# Motor_Controller.net
KiCad netlist of a schematic drawn in Altium Designer
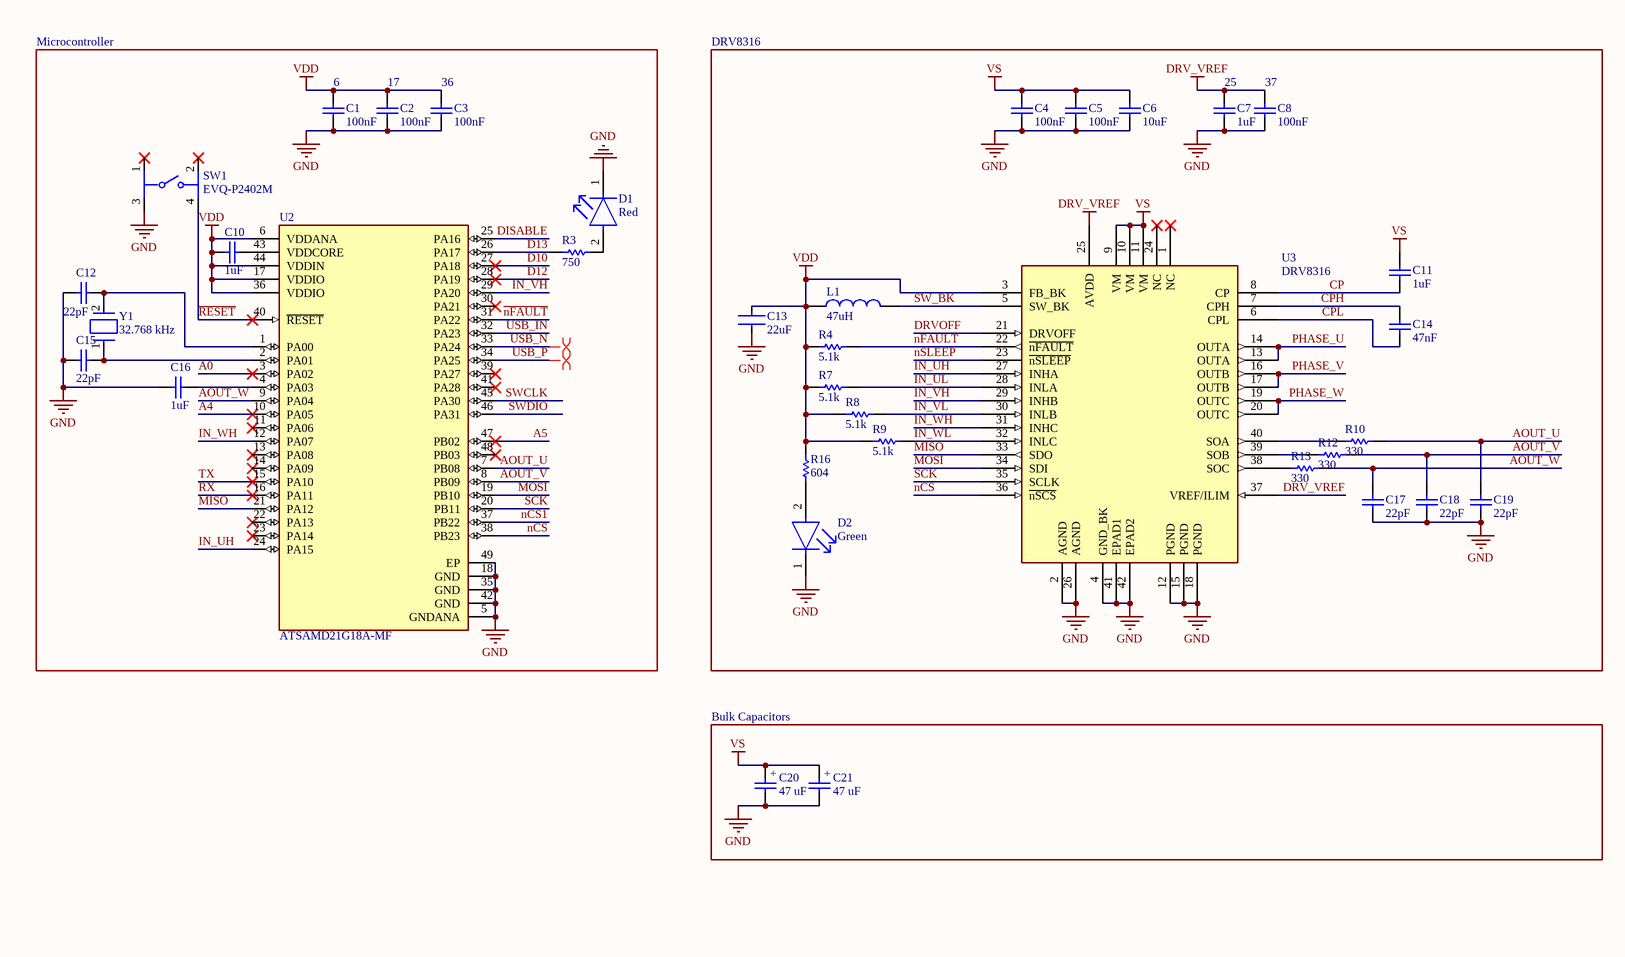
[diagram p0: Motor Controller.SchDoc, left]
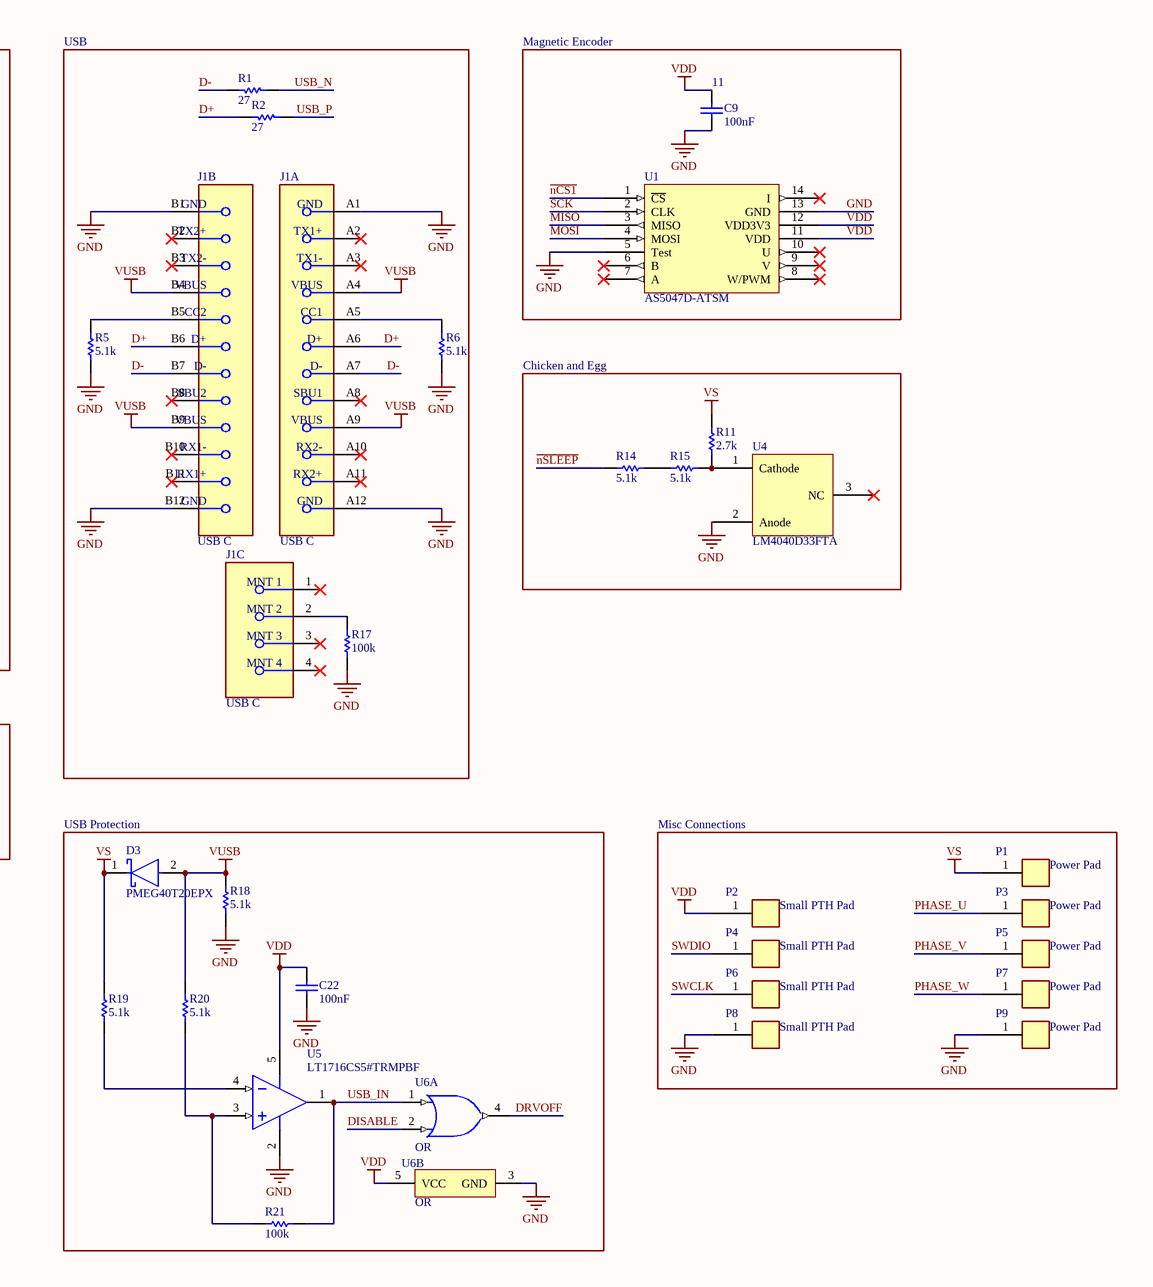
[diagram p1: Motor Controller.SchDoc, right]

(export (version "E")
  (design (tool "Eeschema 10.0.6"))
  (components
    (comp (ref "C1")
      (value "100nF")
      (footprint "0402CAP")
      (libsource (lib "Main") (part "GCM155R71H104KE02D"))
    )
    (comp (ref "C2")
      (value "100nF")
      (footprint "0402CAP")
      (libsource (lib "Main") (part "GCM155R71H104KE02D"))
    )
    (comp (ref "C3")
      (value "100nF")
      (footprint "0402CAP")
      (libsource (lib "Main") (part "GCM155R71H104KE02D"))
    )
    (comp (ref "C4")
      (value "100nF")
      (footprint "0402CAP")
      (libsource (lib "Main") (part "GCM155R71H104KE02D"))
    )
    (comp (ref "C5")
      (value "100nF")
      (footprint "0402CAP")
      (libsource (lib "Main") (part "GCM155R71H104KE02D"))
    )
    (comp (ref "C6")
      (value "10uF")
      (footprint "FP-GRT31C-0_2-IPC_B")
      (libsource (lib "Main") (part "GRT31CR61H106ME01L"))
    )
    (comp (ref "C7") (value "1uF") (footprint "0603CAP") (libsource (lib "Main") (part "GRT188R61H105ME13D")))
    (comp (ref "C8")
      (value "100nF")
      (footprint "0402CAP")
      (libsource (lib "Main") (part "GCM155R71H104KE02D"))
    )
    (comp (ref "C9")
      (value "100nF")
      (footprint "0402CAP")
      (libsource (lib "Main") (part "GCM155R71H104KE02D"))
    )
    (comp (ref "C10")
      (value "1uF")
      (footprint "0603CAP")
      (libsource (lib "Main") (part "GRT188R61H105ME13D"))
    )
    (comp (ref "C11")
      (value "1uF")
      (footprint "0603CAP")
      (libsource (lib "Main") (part "GRT188R61H105ME13D"))
    )
    (comp (ref "C12")
      (value "22pF")
      (footprint "0402CAP")
      (libsource (lib "Main") (part "C0402C220J5GAC7411"))
    )
    (comp (ref "C13")
      (value "22uF")
      (footprint "FP-GRM319-0_15-MFG")
      (description "Multilayer Ceramic Capacitors 22uF ±10% 16V X7R SMD 1210")
      (fields (field (name "VOLTAGE") "16V") (field (name "TOLERANCE") "10%"))
      (libsource (lib "Main") (part "GRM319R61C226ME15D"))
    )
    (comp (ref "C14")
      (value "47nF")
      (footprint "FP-GRM155-0_05-MFG")
      (description "Chip Capacitor, 47 nF, +/- 10%, 50 V, -55 to 125 degC, 0402 (1005 Metric), RoHS, Tape and Reel")
      (fields (field (name "TOLERANCE") "±10%") (field (name "MANUFACTURER") "TDK"))
      (libsource (lib "Main") (part "GRM155R71H473KE14D"))
    )
    (comp (ref "C15")
      (value "22pF")
      (footprint "0402CAP")
      (libsource (lib "Main") (part "C0402C220J5GAC7411"))
    )
    (comp (ref "C16")
      (value "1uF")
      (footprint "0603CAP")
      (libsource (lib "Main") (part "GRT188R61H105ME13D"))
    )
    (comp (ref "C17")
      (value "22pF")
      (footprint "0402CAP")
      (libsource (lib "Main") (part "C0402C220J5GAC7411"))
    )
    (comp (ref "C18")
      (value "22pF")
      (footprint "0402CAP")
      (libsource (lib "Main") (part "C0402C220J5GAC7411"))
    )
    (comp (ref "C19")
      (value "22pF")
      (footprint "0402CAP")
      (libsource (lib "Main") (part "C0402C220J5GAC7411"))
    )
    (comp (ref "C20")
      (value "47 uF")
      (footprint "CAPAE7866X61N")
      (libsource (lib "Main") (part "EEE-FT1H470AL"))
    )
    (comp (ref "C21")
      (value "47 uF")
      (footprint "CAPAE7866X61N")
      (libsource (lib "Main") (part "EEE-FT1H470AL"))
    )
    (comp (ref "C22")
      (value "100nF")
      (footprint "0402CAP")
      (libsource (lib "Main") (part "GCM155R71H104KE02D"))
    )
    (comp (ref "D1")
      (value "Red")
      (footprint "FP-APT1608LSECK-J3-PRV-MFG")
      (description "LED RED CLEAR 2SMD")
      (libsource (lib "Main") (part "APT1608LSECK/J3-PRV"))
    )
    (comp (ref "D2")
      (value "Green")
      (footprint "FP-APT1608MGC-MFG")
      (description "LED GREEN CLEAR CHIP SMD")
      (libsource (lib "Main") (part "APT1608MGC"))
    )
    (comp (ref "D3")
      (value "PMEG40T20EPX")
      (footprint "SODFL470X110-2N")
      (libsource (lib "Main") (part "PMEG40T20EPX"))
    )
    (comp (ref "J1")
      (value "USB C")
      (footprint "FP-1054500101-MFG")
      (description "CONN RCP USB3.1 TYPEC 24P SMD RA")
      (fields
        (field (name "MANUFACTURER") "Molex")
        (field (name "OCTOPART") "https://octopart.com/105450-0101-molex-68082325")
      )
      (libsource (lib "Main") (part "1054500101"))
    )
    (comp (ref "L1")
      (value "47uH")
      (footprint "INDC3225X25N")
      (libsource (lib "Main") (part "L1210R470KDWIT"))
    )
    (comp (ref "P1") (value "Power Pad") (footprint "Power Pad") (libsource (lib "Main") (part "Power Pad")))
    (comp (ref "P2")
      (value "Small PTH Pad")
      (footprint "Small PTH Pad")
      (libsource (lib "Main") (part "Small PTH Pad"))
    )
    (comp (ref "P3") (value "Power Pad") (footprint "Power Pad") (libsource (lib "Main") (part "Power Pad")))
    (comp (ref "P4")
      (value "Small PTH Pad")
      (footprint "Small PTH Pad")
      (libsource (lib "Main") (part "Small PTH Pad"))
    )
    (comp (ref "P5") (value "Power Pad") (footprint "Power Pad") (libsource (lib "Main") (part "Power Pad")))
    (comp (ref "P6")
      (value "Small PTH Pad")
      (footprint "Small PTH Pad")
      (libsource (lib "Main") (part "Small PTH Pad"))
    )
    (comp (ref "P7") (value "Power Pad") (footprint "Power Pad") (libsource (lib "Main") (part "Power Pad")))
    (comp (ref "P8")
      (value "Small PTH Pad")
      (footprint "Small PTH Pad")
      (libsource (lib "Main") (part "Small PTH Pad"))
    )
    (comp (ref "P9") (value "Power Pad") (footprint "Power Pad") (libsource (lib "Main") (part "Power Pad")))
    (comp (ref "R1")
      (value "27")
      (footprint "RESC1005X40X25LL05T05")
      (libsource (lib "Main") (part "ERJ2RKD27R0X"))
    )
    (comp (ref "R2")
      (value "27")
      (footprint "RESC1005X40X25LL05T05")
      (libsource (lib "Main") (part "ERJ2RKD27R0X"))
    )
    (comp (ref "R3")
      (value "750")
      (footprint "RESC1005X40X25LL05T05")
      (libsource (lib "Main") (part "ERJ-2RKF7500X"))
    )
    (comp (ref "R4")
      (value "5.1k")
      (footprint "RESC1005X40X25LL05T05")
      (fields (field (name "TOLERANCE") "1%") (field (name "PARTNUMBER") "ERJ-2RKF4701X"))
      (libsource (lib "Main") (part "ERJ-2RKF5101X"))
    )
    (comp (ref "R5")
      (value "5.1k")
      (footprint "RESC1005X40X25LL05T05")
      (fields (field (name "TOLERANCE") "1%") (field (name "PARTNUMBER") "ERJ-2RKF4701X"))
      (libsource (lib "Main") (part "ERJ-2RKF5101X"))
    )
    (comp (ref "R6")
      (value "5.1k")
      (footprint "RESC1005X40X25LL05T05")
      (fields (field (name "TOLERANCE") "1%") (field (name "PARTNUMBER") "ERJ-2RKF4701X"))
      (libsource (lib "Main") (part "ERJ-2RKF5101X"))
    )
    (comp (ref "R7")
      (value "5.1k")
      (footprint "RESC1005X40X25LL05T05")
      (fields (field (name "TOLERANCE") "1%") (field (name "PARTNUMBER") "ERJ-2RKF4701X"))
      (libsource (lib "Main") (part "ERJ-2RKF5101X"))
    )
    (comp (ref "R8")
      (value "5.1k")
      (footprint "RESC1005X40X25LL05T05")
      (fields (field (name "TOLERANCE") "1%") (field (name "PARTNUMBER") "ERJ-2RKF4701X"))
      (libsource (lib "Main") (part "ERJ-2RKF5101X"))
    )
    (comp (ref "R9")
      (value "5.1k")
      (footprint "RESC1005X40X25LL05T05")
      (fields (field (name "TOLERANCE") "1%") (field (name "PARTNUMBER") "ERJ-2RKF4701X"))
      (libsource (lib "Main") (part "ERJ-2RKF5101X"))
    )
    (comp (ref "R10")
      (value "330")
      (footprint "RESC1005X40X25LL05T05")
      (fields (field (name "MANUFACTURER") "Panasonic") (field (name "PART NUMBER") "ERJ2RKF3300X"))
      (libsource (lib "Main") (part "ERJ2RKF3300X"))
    )
    (comp (ref "R11")
      (value "2.7k")
      (footprint "RESC1005X40X25LL05T05")
      (fields (field (name "PART NUMBER") "ERJ2RKF2701X") (field (name "MANUFACTURER") "Panasonic"))
      (libsource (lib "Main") (part "ERJ2RKF2701X"))
    )
    (comp (ref "R12")
      (value "330")
      (footprint "RESC1005X40X25LL05T05")
      (fields (field (name "MANUFACTURER") "Panasonic") (field (name "PART NUMBER") "ERJ2RKF3300X"))
      (libsource (lib "Main") (part "ERJ2RKF3300X"))
    )
    (comp (ref "R13")
      (value "330")
      (footprint "RESC1005X40X25LL05T05")
      (fields (field (name "MANUFACTURER") "Panasonic") (field (name "PART NUMBER") "ERJ2RKF3300X"))
      (libsource (lib "Main") (part "ERJ2RKF3300X"))
    )
    (comp (ref "R14")
      (value "5.1k")
      (footprint "RESC1005X40X25LL05T05")
      (fields (field (name "TOLERANCE") "1%") (field (name "PARTNUMBER") "ERJ-2RKF4701X"))
      (libsource (lib "Main") (part "ERJ-2RKF5101X"))
    )
    (comp (ref "R15")
      (value "5.1k")
      (footprint "RESC1005X40X25LL05T05")
      (fields (field (name "TOLERANCE") "1%") (field (name "PARTNUMBER") "ERJ-2RKF4701X"))
      (libsource (lib "Main") (part "ERJ-2RKF5101X"))
    )
    (comp (ref "R16")
      (value "604")
      (footprint "RESC1005X40X25LL05T05")
      (fields (field (name "PART NUMBER") "ERJ-2RKF6040X") (field (name "MANUFACTURER") "Panasonic"))
      (libsource (lib "Main") (part "ERJ-2RKF6040X"))
    )
    (comp (ref "R17")
      (value "100k")
      (footprint "RESC1005X40X25LL05T05")
      (libsource (lib "Main") (part "ERJ2RHD1003X"))
    )
    (comp (ref "R18")
      (value "5.1k")
      (footprint "RESC1005X40X25LL05T05")
      (fields (field (name "TOLERANCE") "1%") (field (name "PARTNUMBER") "ERJ-2RKF4701X"))
      (libsource (lib "Main") (part "ERJ-2RKF5101X"))
    )
    (comp (ref "R19")
      (value "5.1k")
      (footprint "RESC1005X40X25LL05T05")
      (fields (field (name "TOLERANCE") "1%") (field (name "PARTNUMBER") "ERJ-2RKF4701X"))
      (libsource (lib "Main") (part "ERJ-2RKF5101X"))
    )
    (comp (ref "R20")
      (value "5.1k")
      (footprint "RESC1005X40X25LL05T05")
      (fields (field (name "TOLERANCE") "1%") (field (name "PARTNUMBER") "ERJ-2RKF4701X"))
      (libsource (lib "Main") (part "ERJ-2RKF5101X"))
    )
    (comp (ref "R21")
      (value "100k")
      (footprint "RESC1005X40X25LL05T05")
      (libsource (lib "Main") (part "ERJ2RHD1003X"))
    )
    (comp (ref "SW1")
      (value "EVQ-P2402M")
      (footprint "EVQ-P2402M")
      (libsource (lib "Main") (part "EVQ-P2402M"))
    )
    (comp (ref "U1")
      (value "AS5047D-ATSM")
      (footprint "TSOP65P640X120-14N")
      (libsource (lib "Main") (part "AS5047D-ATSM"))
    )
    (comp (ref "U2")
      (value "ATSAMD21G18A-MF")
      (footprint "QFN-48")
      (libsource (lib "Main") (part "ATSAMD21G18A-MF"))
    )
    (comp (ref "U3")
      (value "DRV8316")
      (footprint "QFN50P500X700X100_HS-41L")
      (libsource (lib "Main") (part "DRV8316"))
    )
    (comp (ref "U4")
      (value "LM4040D33FTA")
      (footprint "SOT65P210X100-3N")
      (libsource (lib "Main") (part "LM4040D33FTA"))
    )
    (comp (ref "U5")
      (value "LT1716CS5#TRMPBF")
      (footprint "SOT95P280X100-5N")
      (fields (field (name "GENERIC PART NUMBER") "LT1716") (field (name "MANUFACTURER") "Linear Technology"))
      (libsource (lib "Main") (part "LT1716CS5#TRMPBF"))
    )
    (comp (ref "U6")
      (value "OR")
      (footprint "DBV0005A_M")
      (description "Single Power Supply 2-INPUT POSITIVE OR GATE with Logic Level Shifter, DBV0005A, LARGE T&R")
      (fields
        (field (name "GENERIC PART NUMBER") "SN74LV1T32")
        (field (name "MANUFACTURER") "Texas Instruments")
      )
      (libsource (lib "Main") (part "SN74LV1T32DBVR"))
    )
    (comp (ref "Y1")
      (value "32.768 kHz")
      (footprint "ABS05W-32.768KHZ-D-2-T")
      (description "Crystal Oscillator")
      (libsource (lib "Main") (part "ABS05W-32.768KHZ-D-2-T"))
    )
  )
  (nets
    (net (code "1") (name "/A0") (class "Default")
      (node (ref "U2") (pin "3") (pinfunction "PA02_3") (pintype "bidirectional+no_connect"))
    )
    (net (code "2") (name "/A4") (class "Default")
      (node (ref "U2") (pin "10") (pinfunction "PA05_10") (pintype "bidirectional+no_connect"))
    )
    (net (code "3") (name "/A5") (class "Default")
      (node (ref "U2") (pin "47") (pinfunction "PB02_47") (pintype "bidirectional+no_connect"))
    )
    (net (code "4") (name "/AOUT_U") (class "Default")
      (node (ref "C19") (pin "2") (pinfunction "2_2") (pintype "passive"))
      (node (ref "R10") (pin "2") (pinfunction "2_2") (pintype "passive"))
      (node (ref "U2") (pin "7") (pinfunction "PB08_7") (pintype "bidirectional"))
    )
    (net (code "5") (name "/AOUT_V") (class "Default")
      (node (ref "C18") (pin "2") (pinfunction "2_2") (pintype "passive"))
      (node (ref "R12") (pin "2") (pinfunction "2_2") (pintype "passive"))
      (node (ref "U2") (pin "8") (pinfunction "PB09_8") (pintype "bidirectional"))
    )
    (net (code "6") (name "/AOUT_W") (class "Default")
      (node (ref "C17") (pin "2") (pinfunction "2_2") (pintype "passive"))
      (node (ref "R13") (pin "2") (pinfunction "2_2") (pintype "passive"))
      (node (ref "U2") (pin "9") (pinfunction "PA04_9") (pintype "bidirectional"))
    )
    (net (code "7") (name "/CP") (class "Default")
      (node (ref "C11") (pin "1") (pinfunction "1_1") (pintype "passive"))
      (node (ref "U3") (pin "8") (pinfunction "CP_8") (pintype "power_in"))
    )
    (net (code "8") (name "/CPH") (class "Default")
      (node (ref "C14") (pin "2") (pinfunction "2_2") (pintype "passive"))
      (node (ref "U3") (pin "7") (pinfunction "CPH_7") (pintype "power_in"))
    )
    (net (code "9") (name "/CPL") (class "Default")
      (node (ref "C14") (pin "1") (pinfunction "1_1") (pintype "passive"))
      (node (ref "U3") (pin "6") (pinfunction "CPL_6") (pintype "power_in"))
    )
    (net (code "10") (name "/D+") (class "Default")
      (node (ref "J1") (pin "A6") (pinfunction "D+_A6") (pintype "passive"))
      (node (ref "J1") (pin "B6") (pinfunction "D+_B6") (pintype "passive"))
      (node (ref "R2") (pin "2") (pinfunction "2_2") (pintype "passive"))
    )
    (net (code "11") (name "/D-") (class "Default")
      (node (ref "J1") (pin "A7") (pinfunction "D-_A7") (pintype "passive"))
      (node (ref "J1") (pin "B7") (pinfunction "D-_B7") (pintype "passive"))
      (node (ref "R1") (pin "2") (pinfunction "2_2") (pintype "passive"))
    )
    (net (code "12") (name "/D10") (class "Default")
      (node (ref "U2") (pin "27") (pinfunction "PA18_27") (pintype "bidirectional+no_connect"))
    )
    (net (code "13") (name "/D12") (class "Default")
      (node (ref "U2") (pin "28") (pinfunction "PA19_28") (pintype "bidirectional+no_connect"))
    )
    (net (code "14") (name "/D13") (class "Default")
      (node (ref "R3") (pin "1") (pinfunction "1_1") (pintype "passive"))
      (node (ref "U2") (pin "26") (pinfunction "PA17_26") (pintype "bidirectional"))
    )
    (net (code "15") (name "/DISABLE") (class "Default")
      (node (ref "U2") (pin "25") (pinfunction "PA16_25") (pintype "bidirectional"))
      (node (ref "U6") (pin "2") (pinfunction "B_2") (pintype "input"))
    )
    (net (code "16") (name "/DRVOFF") (class "Default")
      (node (ref "U3") (pin "21") (pinfunction "DRVOFF_21") (pintype "input"))
      (node (ref "U6") (pin "4") (pinfunction "Y_4") (pintype "output"))
    )
    (net (code "17") (name "/IN_UH") (class "Default")
      (node (ref "U2") (pin "24") (pinfunction "PA15_24") (pintype "bidirectional"))
      (node (ref "U3") (pin "27") (pinfunction "INHA_27") (pintype "input"))
    )
    (net (code "18") (name "/IN_UL") (class "Default")
      (node (ref "R7") (pin "2") (pinfunction "2_2") (pintype "passive"))
      (node (ref "U3") (pin "28") (pinfunction "INLA_28") (pintype "input"))
    )
    (net (code "19") (name "/IN_VH") (class "Default")
      (node (ref "U2") (pin "29") (pinfunction "PA20_29") (pintype "bidirectional"))
      (node (ref "U3") (pin "29") (pinfunction "INHB_29") (pintype "input"))
    )
    (net (code "20") (name "/IN_VL") (class "Default")
      (node (ref "R8") (pin "2") (pinfunction "2_2") (pintype "passive"))
      (node (ref "U3") (pin "30") (pinfunction "INLB_30") (pintype "input"))
    )
    (net (code "21") (name "/IN_WH") (class "Default")
      (node (ref "U2") (pin "12") (pinfunction "PA07_12") (pintype "bidirectional"))
      (node (ref "U3") (pin "31") (pinfunction "INHC_31") (pintype "input"))
    )
    (net (code "22") (name "/IN_WL") (class "Default")
      (node (ref "R9") (pin "2") (pinfunction "2_2") (pintype "passive"))
      (node (ref "U3") (pin "32") (pinfunction "INLC_32") (pintype "input"))
    )
    (net (code "23") (name "/MISO") (class "Default")
      (node (ref "U1") (pin "3") (pinfunction "MISO_3") (pintype "output"))
      (node (ref "U2") (pin "21") (pinfunction "PA12_21") (pintype "bidirectional"))
      (node (ref "U3") (pin "33") (pinfunction "SDO_33") (pintype "output"))
    )
    (net (code "24") (name "/MOSI") (class "Default")
      (node (ref "U1") (pin "4") (pinfunction "MOSI_4") (pintype "input"))
      (node (ref "U2") (pin "19") (pinfunction "PB10_19") (pintype "bidirectional"))
      (node (ref "U3") (pin "34") (pinfunction "SDI_34") (pintype "input"))
    )
    (net (code "25") (name "/PHASE_U") (class "Default")
      (node (ref "P3") (pin "1") (pintype "passive"))
      (node (ref "U3") (pin "13") (pinfunction "OUTA_13") (pintype "output"))
      (node (ref "U3") (pin "14") (pinfunction "OUTA_14") (pintype "output"))
    )
    (net (code "26") (name "/PHASE_V") (class "Default")
      (node (ref "P5") (pin "1") (pintype "passive"))
      (node (ref "U3") (pin "16") (pinfunction "OUTB_16") (pintype "output"))
      (node (ref "U3") (pin "17") (pinfunction "OUTB_17") (pintype "output"))
    )
    (net (code "27") (name "/PHASE_W") (class "Default")
      (node (ref "P7") (pin "1") (pintype "passive"))
      (node (ref "U3") (pin "19") (pinfunction "OUTC_19") (pintype "output"))
      (node (ref "U3") (pin "20") (pinfunction "OUTC_20") (pintype "output"))
    )
    (net (code "28") (name "/RESET") (class "Default")
      (node (ref "SW1") (pin "4") (pinfunction "4_4") (pintype "passive"))
      (node (ref "U2") (pin "40") (pinfunction "~{RESET}_40") (pintype "input"))
    )
    (net (code "29") (name "/RX") (class "Default")
      (node (ref "U2") (pin "16") (pinfunction "PA11_16") (pintype "bidirectional+no_connect"))
    )
    (net (code "30") (name "/SCK") (class "Default")
      (node (ref "U1") (pin "2") (pinfunction "CLK_2") (pintype "input"))
      (node (ref "U2") (pin "20") (pinfunction "PB11_20") (pintype "bidirectional"))
      (node (ref "U3") (pin "35") (pinfunction "SCLK_35") (pintype "input"))
    )
    (net (code "31") (name "/SWCLK") (class "Default")
      (node (ref "P6") (pin "1") (pintype "passive"))
      (node (ref "U2") (pin "45") (pinfunction "PA30_45") (pintype "bidirectional"))
    )
    (net (code "32") (name "/SWDIO") (class "Default")
      (node (ref "P4") (pin "1") (pintype "passive"))
      (node (ref "U2") (pin "46") (pinfunction "PA31_46") (pintype "bidirectional"))
    )
    (net (code "33") (name "/SW_BK") (class "Default")
      (node (ref "L1") (pin "2") (pintype "passive"))
      (node (ref "U3") (pin "5") (pinfunction "SW_BK_5") (pintype "passive"))
    )
    (net (code "34") (name "/TX") (class "Default")
      (node (ref "U2") (pin "15") (pinfunction "PA10_15") (pintype "bidirectional+no_connect"))
    )
    (net (code "35") (name "/USB_IN") (class "Default")
      (node (ref "R21") (pin "2") (pinfunction "2_2") (pintype "passive"))
      (node (ref "U2") (pin "32") (pinfunction "PA23_32") (pintype "bidirectional"))
      (node (ref "U5") (pin "1") (pinfunction "OUT_1") (pintype "open_collector"))
      (node (ref "U6") (pin "1") (pinfunction "A_1") (pintype "input"))
    )
    (net (code "36") (name "/USB_N") (class "Default")
      (node (ref "R1") (pin "1") (pinfunction "1_1") (pintype "passive"))
      (node (ref "U2") (pin "33") (pinfunction "PA24_33") (pintype "bidirectional"))
    )
    (net (code "37") (name "/USB_P") (class "Default")
      (node (ref "R2") (pin "1") (pinfunction "1_1") (pintype "passive"))
      (node (ref "U2") (pin "34") (pinfunction "PA25_34") (pintype "bidirectional"))
    )
    (net (code "38") (name "/nCS") (class "Default")
      (node (ref "U2") (pin "38") (pinfunction "PB23_38") (pintype "bidirectional"))
      (node (ref "U3") (pin "36") (pinfunction "nSCS_36") (pintype "input"))
    )
    (net (code "39") (name "/nCS1") (class "Default")
      (node (ref "U1") (pin "1") (pinfunction "CS_1") (pintype "input"))
      (node (ref "U2") (pin "37") (pinfunction "PB22_37") (pintype "bidirectional"))
    )
    (net (code "40") (name "/nFAULT") (class "Default")
      (node (ref "R4") (pin "2") (pinfunction "2_2") (pintype "passive"))
      (node (ref "U2") (pin "31") (pinfunction "PA22_31") (pintype "bidirectional"))
      (node (ref "U3") (pin "22") (pinfunction "nFAULT_22") (pintype "output"))
    )
    (net (code "41") (name "/nSLEEP") (class "Default")
      (node (ref "R14") (pin "1") (pinfunction "1_1") (pintype "passive"))
      (node (ref "U3") (pin "23") (pinfunction "nSLEEP_23") (pintype "passive"))
    )
    (net (code "42") (name "DRV_VREF") (class "Default")
      (node (ref "C7") (pin "2") (pinfunction "2_2") (pintype "passive"))
      (node (ref "C8") (pin "2") (pinfunction "2_2") (pintype "passive"))
      (node (ref "U3") (pin "25") (pinfunction "AVDD_25") (pintype "power_in"))
      (node (ref "U3") (pin "37") (pinfunction "VREF/ILIM_37") (pintype "input"))
    )
    (net (code "43") (name "GND") (class "Default")
      (node (ref "C1") (pin "1") (pinfunction "1_1") (pintype "passive"))
      (node (ref "C12") (pin "1") (pinfunction "1_1") (pintype "passive"))
      (node (ref "C13") (pin "2") (pinfunction "2_2") (pintype "passive"))
      (node (ref "C15") (pin "1") (pinfunction "1_1") (pintype "passive"))
      (node (ref "C16") (pin "1") (pinfunction "1_1") (pintype "passive"))
      (node (ref "C17") (pin "1") (pinfunction "1_1") (pintype "passive"))
      (node (ref "C18") (pin "1") (pinfunction "1_1") (pintype "passive"))
      (node (ref "C19") (pin "1") (pinfunction "1_1") (pintype "passive"))
      (node (ref "C2") (pin "1") (pinfunction "1_1") (pintype "passive"))
      (node (ref "C20") (pin "2") (pinfunction "2_2") (pintype "passive"))
      (node (ref "C21") (pin "2") (pinfunction "2_2") (pintype "passive"))
      (node (ref "C22") (pin "1") (pinfunction "1_1") (pintype "passive"))
      (node (ref "C3") (pin "1") (pinfunction "1_1") (pintype "passive"))
      (node (ref "C4") (pin "1") (pinfunction "1_1") (pintype "passive"))
      (node (ref "C5") (pin "1") (pinfunction "1_1") (pintype "passive"))
      (node (ref "C6") (pin "1") (pinfunction "1_1") (pintype "passive"))
      (node (ref "C7") (pin "1") (pinfunction "1_1") (pintype "passive"))
      (node (ref "C8") (pin "1") (pinfunction "1_1") (pintype "passive"))
      (node (ref "C9") (pin "1") (pinfunction "1_1") (pintype "passive"))
      (node (ref "D1") (pin "1") (pinfunction "C_1") (pintype "passive"))
      (node (ref "D2") (pin "1") (pinfunction "C_1") (pintype "passive"))
      (node (ref "J1") (pin "A1") (pinfunction "GND_A1") (pintype "passive"))
      (node (ref "J1") (pin "A12") (pinfunction "GND_A12") (pintype "passive"))
      (node (ref "J1") (pin "B1") (pinfunction "GND_B1") (pintype "passive"))
      (node (ref "J1") (pin "B12") (pinfunction "GND_B12") (pintype "passive"))
      (node (ref "P8") (pin "1") (pintype "passive"))
      (node (ref "P9") (pin "1") (pintype "passive"))
      (node (ref "R17") (pin "1") (pinfunction "1_1") (pintype "passive"))
      (node (ref "R18") (pin "1") (pinfunction "1_1") (pintype "passive"))
      (node (ref "R5") (pin "2") (pinfunction "2_2") (pintype "passive"))
      (node (ref "R6") (pin "2") (pinfunction "2_2") (pintype "passive"))
      (node (ref "SW1") (pin "3") (pinfunction "3_3") (pintype "passive"))
      (node (ref "U1") (pin "13") (pinfunction "GND_13") (pintype "power_in"))
      (node (ref "U1") (pin "5") (pinfunction "Test_5") (pintype "passive"))
      (node (ref "U2") (pin "18") (pinfunction "GND_18") (pintype "power_in"))
      (node (ref "U2") (pin "35") (pinfunction "GND_35") (pintype "power_in"))
      (node (ref "U2") (pin "42") (pinfunction "GND_42") (pintype "power_in"))
      (node (ref "U2") (pin "49") (pinfunction "EP_49") (pintype "power_in"))
      (node (ref "U2") (pin "5") (pinfunction "GNDANA_5") (pintype "power_in"))
      (node (ref "U3") (pin "12") (pinfunction "PGND_12") (pintype "power_in"))
      (node (ref "U3") (pin "15") (pinfunction "PGND_15") (pintype "power_in"))
      (node (ref "U3") (pin "18") (pinfunction "PGND_18") (pintype "power_in"))
      (node (ref "U3") (pin "2") (pinfunction "AGND_2") (pintype "power_in"))
      (node (ref "U3") (pin "26") (pinfunction "AGND_26") (pintype "power_in"))
      (node (ref "U3") (pin "4") (pinfunction "GND_BK_4") (pintype "power_in"))
      (node (ref "U3") (pin "41") (pinfunction "EPAD1_41") (pintype "power_in"))
      (node (ref "U3") (pin "42") (pinfunction "EPAD2_42") (pintype "power_in"))
      (node (ref "U4") (pin "2") (pinfunction "Anode_2") (pintype "passive"))
      (node (ref "U5") (pin "2") (pinfunction "V-_2") (pintype "power_in"))
      (node (ref "U6") (pin "3") (pinfunction "GND_3") (pintype "power_in"))
    )
    (net (code "44") (name "Net-(D1-A)") (class "Default")
      (node (ref "D1") (pin "2") (pinfunction "A_2") (pintype "passive"))
      (node (ref "R3") (pin "2") (pinfunction "2_2") (pintype "passive"))
    )
    (net (code "45") (name "Net-(D2-A)") (class "Default")
      (node (ref "D2") (pin "2") (pinfunction "A_2") (pintype "passive"))
      (node (ref "R16") (pin "1") (pinfunction "1_1") (pintype "passive"))
    )
    (net (code "46") (name "Net-(J1A-CC1)") (class "Default")
      (node (ref "J1") (pin "A5") (pinfunction "CC1_A5") (pintype "passive"))
      (node (ref "R6") (pin "1") (pinfunction "1_1") (pintype "passive"))
    )
    (net (code "47") (name "Net-(J1B-CC2)") (class "Default")
      (node (ref "J1") (pin "B5") (pinfunction "CC2_B5") (pintype "passive"))
      (node (ref "R5") (pin "1") (pinfunction "1_1") (pintype "passive"))
    )
    (net (code "48") (name "Net-(J1C-MNT_2)") (class "Default")
      (node (ref "J1") (pin "2") (pinfunction "MNT_2_2") (pintype "passive"))
      (node (ref "R17") (pin "2") (pinfunction "2_2") (pintype "passive"))
    )
    (net (code "49") (name "Net-(R14-Pad2)") (class "Default")
      (node (ref "R14") (pin "2") (pinfunction "2_2") (pintype "passive"))
      (node (ref "R15") (pin "1") (pinfunction "1_1") (pintype "passive"))
    )
    (net (code "50") (name "Net-(U2-PA00)") (class "Default")
      (node (ref "C12") (pin "2") (pinfunction "2_2") (pintype "passive"))
      (node (ref "U2") (pin "1") (pinfunction "PA00_1") (pintype "bidirectional"))
      (node (ref "Y1") (pin "2") (pinfunction "2_2") (pintype "passive"))
    )
    (net (code "51") (name "Net-(U2-PA01)") (class "Default")
      (node (ref "C15") (pin "2") (pinfunction "2_2") (pintype "passive"))
      (node (ref "U2") (pin "2") (pinfunction "PA01_2") (pintype "bidirectional"))
      (node (ref "Y1") (pin "1") (pinfunction "1_1") (pintype "passive"))
    )
    (net (code "52") (name "Net-(U2-PA03)") (class "Default")
      (node (ref "C16") (pin "2") (pinfunction "2_2") (pintype "passive"))
      (node (ref "U2") (pin "4") (pinfunction "PA03_4") (pintype "bidirectional"))
    )
    (net (code "53") (name "Net-(U2-VDDCORE)") (class "Default")
      (node (ref "C10") (pin "1") (pinfunction "1_1") (pintype "passive"))
      (node (ref "U2") (pin "43") (pinfunction "VDDCORE_43") (pintype "power_in"))
    )
    (net (code "54") (name "Net-(U3-SOA)") (class "Default")
      (node (ref "R10") (pin "1") (pinfunction "1_1") (pintype "passive"))
      (node (ref "U3") (pin "40") (pinfunction "SOA_40") (pintype "output"))
    )
    (net (code "55") (name "Net-(U3-SOB)") (class "Default")
      (node (ref "R12") (pin "1") (pinfunction "1_1") (pintype "passive"))
      (node (ref "U3") (pin "39") (pinfunction "SOB_39") (pintype "output"))
    )
    (net (code "56") (name "Net-(U3-SOC)") (class "Default")
      (node (ref "R13") (pin "1") (pinfunction "1_1") (pintype "passive"))
      (node (ref "U3") (pin "38") (pinfunction "SOC_38") (pintype "output"))
    )
    (net (code "57") (name "Net-(U4-Cathode)") (class "Default")
      (node (ref "R11") (pin "1") (pinfunction "1_1") (pintype "passive"))
      (node (ref "R15") (pin "2") (pinfunction "2_2") (pintype "passive"))
      (node (ref "U4") (pin "1") (pinfunction "Cathode_1") (pintype "passive"))
    )
    (net (code "58") (name "Net-(U5-+IN)") (class "Default")
      (node (ref "R20") (pin "1") (pinfunction "1_1") (pintype "passive"))
      (node (ref "R21") (pin "1") (pinfunction "1_1") (pintype "passive"))
      (node (ref "U5") (pin "3") (pinfunction "+IN_3") (pintype "input"))
    )
    (net (code "59") (name "Net-(U5--IN)") (class "Default")
      (node (ref "R19") (pin "1") (pinfunction "1_1") (pintype "passive"))
      (node (ref "U5") (pin "4") (pinfunction "-IN_4") (pintype "input"))
    )
    (net (code "60") (name "VDD") (class "Default")
      (node (ref "C1") (pin "2") (pinfunction "2_2") (pintype "passive"))
      (node (ref "C10") (pin "2") (pinfunction "2_2") (pintype "passive"))
      (node (ref "C13") (pin "1") (pinfunction "1_1") (pintype "passive"))
      (node (ref "C2") (pin "2") (pinfunction "2_2") (pintype "passive"))
      (node (ref "C22") (pin "2") (pinfunction "2_2") (pintype "passive"))
      (node (ref "C3") (pin "2") (pinfunction "2_2") (pintype "passive"))
      (node (ref "C9") (pin "2") (pinfunction "2_2") (pintype "passive"))
      (node (ref "L1") (pin "1") (pintype "passive"))
      (node (ref "P2") (pin "1") (pintype "passive"))
      (node (ref "R16") (pin "2") (pinfunction "2_2") (pintype "passive"))
      (node (ref "R4") (pin "1") (pinfunction "1_1") (pintype "passive"))
      (node (ref "R7") (pin "1") (pinfunction "1_1") (pintype "passive"))
      (node (ref "R8") (pin "1") (pinfunction "1_1") (pintype "passive"))
      (node (ref "R9") (pin "1") (pinfunction "1_1") (pintype "passive"))
      (node (ref "U1") (pin "11") (pinfunction "VDD_11") (pintype "power_in"))
      (node (ref "U1") (pin "12") (pinfunction "VDD3V3_12") (pintype "power_in"))
      (node (ref "U2") (pin "17") (pinfunction "VDDIO_17") (pintype "power_in"))
      (node (ref "U2") (pin "36") (pinfunction "VDDIO_36") (pintype "power_in"))
      (node (ref "U2") (pin "44") (pinfunction "VDDIN_44") (pintype "power_in"))
      (node (ref "U2") (pin "6") (pinfunction "VDDANA_6") (pintype "power_in"))
      (node (ref "U3") (pin "3") (pinfunction "FB_BK_3") (pintype "power_in"))
      (node (ref "U5") (pin "5") (pinfunction "V+_5") (pintype "power_in"))
      (node (ref "U6") (pin "5") (pinfunction "VCC_5") (pintype "power_in"))
    )
    (net (code "61") (name "VS") (class "Default")
      (node (ref "C11") (pin "2") (pinfunction "2_2") (pintype "passive"))
      (node (ref "C20") (pin "1") (pinfunction "1_1") (pintype "passive"))
      (node (ref "C21") (pin "1") (pinfunction "1_1") (pintype "passive"))
      (node (ref "C4") (pin "2") (pinfunction "2_2") (pintype "passive"))
      (node (ref "C5") (pin "2") (pinfunction "2_2") (pintype "passive"))
      (node (ref "C6") (pin "2") (pinfunction "2_2") (pintype "passive"))
      (node (ref "D3") (pin "1") (pinfunction "C_1") (pintype "passive"))
      (node (ref "P1") (pin "1") (pintype "passive"))
      (node (ref "R11") (pin "2") (pinfunction "2_2") (pintype "passive"))
      (node (ref "R19") (pin "2") (pinfunction "2_2") (pintype "passive"))
      (node (ref "U3") (pin "10") (pinfunction "VM_10") (pintype "power_in"))
      (node (ref "U3") (pin "11") (pinfunction "VM_11") (pintype "power_in"))
      (node (ref "U3") (pin "9") (pinfunction "VM_9") (pintype "power_in"))
    )
    (net (code "62") (name "VUSB") (class "Default")
      (node (ref "D3") (pin "2") (pinfunction "A_2") (pintype "passive"))
      (node (ref "J1") (pin "A4") (pinfunction "VBUS_A4") (pintype "passive"))
      (node (ref "J1") (pin "A9") (pinfunction "VBUS_A9") (pintype "passive"))
      (node (ref "J1") (pin "B4") (pinfunction "VBUS_B4") (pintype "passive"))
      (node (ref "J1") (pin "B9") (pinfunction "VBUS_B9") (pintype "passive"))
      (node (ref "R18") (pin "2") (pinfunction "2_2") (pintype "passive"))
      (node (ref "R20") (pin "2") (pinfunction "2_2") (pintype "passive"))
    )
    (net (code "63") (name "unconnected-(J1A-RX2+-PadA11)") (class "Default")
      (node (ref "J1") (pin "A11") (pinfunction "RX2+_A11") (pintype "passive+no_connect"))
    )
    (net (code "64") (name "unconnected-(J1A-RX2--PadA10)") (class "Default")
      (node (ref "J1") (pin "A10") (pinfunction "RX2-_A10") (pintype "passive+no_connect"))
    )
    (net (code "65") (name "unconnected-(J1A-SBU1-PadA8)") (class "Default")
      (node (ref "J1") (pin "A8") (pinfunction "SBU1_A8") (pintype "passive+no_connect"))
    )
    (net (code "66") (name "unconnected-(J1A-TX1+-PadA2)") (class "Default")
      (node (ref "J1") (pin "A2") (pinfunction "TX1+_A2") (pintype "passive+no_connect"))
    )
    (net (code "67") (name "unconnected-(J1A-TX1--PadA3)") (class "Default")
      (node (ref "J1") (pin "A3") (pinfunction "TX1-_A3") (pintype "passive+no_connect"))
    )
    (net (code "68") (name "unconnected-(J1B-RX1+-PadB11)") (class "Default")
      (node (ref "J1") (pin "B11") (pinfunction "RX1+_B11") (pintype "passive+no_connect"))
    )
    (net (code "69") (name "unconnected-(J1B-RX1--PadB10)") (class "Default")
      (node (ref "J1") (pin "B10") (pinfunction "RX1-_B10") (pintype "passive+no_connect"))
    )
    (net (code "70") (name "unconnected-(J1B-SBU2-PadB8)") (class "Default")
      (node (ref "J1") (pin "B8") (pinfunction "SBU2_B8") (pintype "passive+no_connect"))
    )
    (net (code "71") (name "unconnected-(J1B-TX2+-PadB2)") (class "Default")
      (node (ref "J1") (pin "B2") (pinfunction "TX2+_B2") (pintype "passive+no_connect"))
    )
    (net (code "72") (name "unconnected-(J1B-TX2--PadB3)") (class "Default")
      (node (ref "J1") (pin "B3") (pinfunction "TX2-_B3") (pintype "passive+no_connect"))
    )
    (net (code "73") (name "unconnected-(J1C-MNT_1-Pad1)") (class "Default")
      (node (ref "J1") (pin "1") (pinfunction "MNT_1_1") (pintype "passive+no_connect"))
    )
    (net (code "74") (name "unconnected-(J1C-MNT_3-Pad3)") (class "Default")
      (node (ref "J1") (pin "3") (pinfunction "MNT_3_3") (pintype "passive+no_connect"))
    )
    (net (code "75") (name "unconnected-(J1C-MNT_4-Pad4)") (class "Default")
      (node (ref "J1") (pin "4") (pinfunction "MNT_4_4") (pintype "passive+no_connect"))
    )
    (net (code "76") (name "unconnected-(SW1-Pad1)") (class "Default")
      (node (ref "SW1") (pin "1") (pinfunction "1_1") (pintype "passive+no_connect"))
    )
    (net (code "77") (name "unconnected-(SW1-Pad2)") (class "Default")
      (node (ref "SW1") (pin "2") (pinfunction "2_2") (pintype "passive+no_connect"))
    )
    (net (code "78") (name "unconnected-(U1-A-Pad7)") (class "Default")
      (node (ref "U1") (pin "7") (pinfunction "A_7") (pintype "output+no_connect"))
    )
    (net (code "79") (name "unconnected-(U1-B-Pad6)") (class "Default")
      (node (ref "U1") (pin "6") (pinfunction "B_6") (pintype "output+no_connect"))
    )
    (net (code "80") (name "unconnected-(U1-I-Pad14)") (class "Default")
      (node (ref "U1") (pin "14") (pinfunction "I_14") (pintype "output+no_connect"))
    )
    (net (code "81") (name "unconnected-(U1-U-Pad10)") (class "Default")
      (node (ref "U1") (pin "10") (pinfunction "U_10") (pintype "output+no_connect"))
    )
    (net (code "82") (name "unconnected-(U1-V-Pad9)") (class "Default")
      (node (ref "U1") (pin "9") (pinfunction "V_9") (pintype "output+no_connect"))
    )
    (net (code "83") (name "unconnected-(U1-W{slash}PWM-Pad8)") (class "Default")
      (node (ref "U1") (pin "8") (pinfunction "W/PWM_8") (pintype "output+no_connect"))
    )
    (net (code "84") (name "unconnected-(U2-PA06-Pad11)") (class "Default")
      (node (ref "U2") (pin "11") (pinfunction "PA06_11") (pintype "bidirectional+no_connect"))
    )
    (net (code "85") (name "unconnected-(U2-PA08-Pad13)") (class "Default")
      (node (ref "U2") (pin "13") (pinfunction "PA08_13") (pintype "bidirectional+no_connect"))
    )
    (net (code "86") (name "unconnected-(U2-PA09-Pad14)") (class "Default")
      (node (ref "U2") (pin "14") (pinfunction "PA09_14") (pintype "bidirectional+no_connect"))
    )
    (net (code "87") (name "unconnected-(U2-PA13-Pad22)") (class "Default")
      (node (ref "U2") (pin "22") (pinfunction "PA13_22") (pintype "bidirectional+no_connect"))
    )
    (net (code "88") (name "unconnected-(U2-PA14-Pad23)") (class "Default")
      (node (ref "U2") (pin "23") (pinfunction "PA14_23") (pintype "bidirectional+no_connect"))
    )
    (net (code "89") (name "unconnected-(U2-PA21-Pad30)") (class "Default")
      (node (ref "U2") (pin "30") (pinfunction "PA21_30") (pintype "bidirectional+no_connect"))
    )
    (net (code "90") (name "unconnected-(U2-PA27-Pad39)") (class "Default")
      (node (ref "U2") (pin "39") (pinfunction "PA27_39") (pintype "bidirectional+no_connect"))
    )
    (net (code "91") (name "unconnected-(U2-PA28-Pad41)") (class "Default")
      (node (ref "U2") (pin "41") (pinfunction "PA28_41") (pintype "bidirectional+no_connect"))
    )
    (net (code "92") (name "unconnected-(U2-PB03-Pad48)") (class "Default")
      (node (ref "U2") (pin "48") (pinfunction "PB03_48") (pintype "bidirectional+no_connect"))
    )
    (net (code "93") (name "unconnected-(U3-NC-Pad1)") (class "Default")
      (node (ref "U3") (pin "1") (pinfunction "NC_1") (pintype "passive+no_connect"))
    )
    (net (code "94") (name "unconnected-(U3-NC-Pad24)") (class "Default")
      (node (ref "U3") (pin "24") (pinfunction "NC_24") (pintype "passive+no_connect"))
    )
    (net (code "95") (name "unconnected-(U4-NC-Pad3)") (class "Default")
      (node (ref "U4") (pin "3") (pinfunction "NC_3") (pintype "passive+no_connect"))
    )
  )
)
